# Sheet.net
KiCad netlist of a schematic drawn in Altium Designer
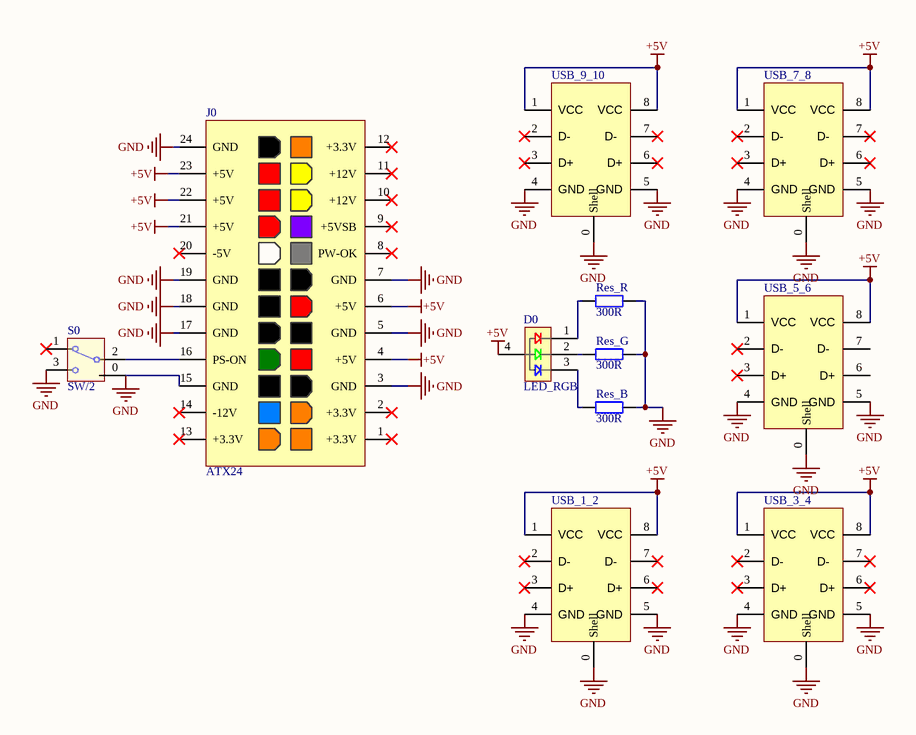
[diagram p0: Sheet.SchDoc]

(export (version "E")
  (design (tool "Eeschema 10.0.6"))
  (components
    (comp (ref "D0") (value "LED_RGB") (footprint "LED_RGB_0805") (libsource (lib "LED") (part "LED_RGB")))
    (comp (ref "J0")
      (value "ATX24")
      (footprint "ATX24-5569")
      (description "ATX24_5569 供电母座")
      (libsource (lib "ATX") (part "ATX24_5569"))
    )
    (comp (ref "Res_B")
      (value "300R")
      (footprint "0805-1")
      (description "贴片电阻")
      (fields (field (name "Comment") "Res1") (field (name "PUBLISHER") "Altium Limited"))
      (libsource (lib "") (part "Res1_1"))
    )
    (comp (ref "Res_G")
      (value "300R")
      (footprint "0805-1")
      (description "贴片电阻")
      (fields (field (name "Comment") "Res1") (field (name "PUBLISHER") "Altium Limited"))
      (libsource (lib "Normal") (part "Res1"))
    )
    (comp (ref "Res_R")
      (value "300R")
      (footprint "0805-1")
      (description "贴片电阻")
      (fields (field (name "Comment") "Res1") (field (name "PUBLISHER") "Altium Limited"))
      (libsource (lib "") (part "Res1_1"))
    )
    (comp (ref "S0")
      (value "SW/2")
      (footprint "SW/2_SIP3_H")
      (description "2档拨动开关")
      (libsource (lib "Switch") (part "SW/2"))
    )
    (comp (ref "USB_1_2")
      (value "USB-A_P/2")
      (footprint "USB-A_P/2")
      (description "USB-A 双层 180度 母座")
      (libsource (lib "USB") (part "USB-A_P/2"))
    )
    (comp (ref "USB_3_4")
      (value "USB-A_P/2")
      (footprint "USB-A_P/2")
      (description "USB-A 双层 180度 母座")
      (libsource (lib "USB") (part "USB-A_P/2"))
    )
    (comp (ref "USB_5_6")
      (value "USB-A_P/2")
      (footprint "USB-A_P/2")
      (description "USB-A 双层 180度 母座")
      (libsource (lib "USB") (part "USB-A_P/2"))
    )
    (comp (ref "USB_7_8")
      (value "USB-A_P/2")
      (footprint "USB-A_P/2")
      (description "USB-A 双层 180度 母座")
      (libsource (lib "USB") (part "USB-A_P/2"))
    )
    (comp (ref "USB_9_10")
      (value "USB-A_P/2")
      (footprint "USB-A_P/2")
      (description "USB-A 双层 180度 母座")
      (libsource (lib "USB") (part "USB-A_P/2"))
    )
  )
  (nets
    (net (code "1") (name "+5V") (class "Default")
      (node (ref "D0") (pin "4") (pinfunction "4_4") (pintype "passive"))
      (node (ref "J0") (pin "21") (pinfunction "+5V_21") (pintype "passive"))
      (node (ref "J0") (pin "22") (pinfunction "+5V_22") (pintype "passive"))
      (node (ref "J0") (pin "23") (pinfunction "+5V_23") (pintype "passive"))
      (node (ref "J0") (pin "4") (pinfunction "+5V_4") (pintype "passive"))
      (node (ref "J0") (pin "6") (pinfunction "+5V_6") (pintype "passive"))
      (node (ref "USB_1_2") (pin "1") (pinfunction "VCC_1") (pintype "passive"))
      (node (ref "USB_1_2") (pin "8") (pinfunction "VCC_8") (pintype "passive"))
      (node (ref "USB_3_4") (pin "1") (pinfunction "VCC_1") (pintype "passive"))
      (node (ref "USB_3_4") (pin "8") (pinfunction "VCC_8") (pintype "passive"))
      (node (ref "USB_5_6") (pin "1") (pinfunction "VCC_1") (pintype "passive"))
      (node (ref "USB_5_6") (pin "8") (pinfunction "VCC_8") (pintype "passive"))
      (node (ref "USB_7_8") (pin "1") (pinfunction "VCC_1") (pintype "passive"))
      (node (ref "USB_7_8") (pin "8") (pinfunction "VCC_8") (pintype "passive"))
      (node (ref "USB_9_10") (pin "1") (pinfunction "VCC_1") (pintype "passive"))
      (node (ref "USB_9_10") (pin "8") (pinfunction "VCC_8") (pintype "passive"))
    )
    (net (code "2") (name "GND") (class "Default")
      (node (ref "J0") (pin "15") (pinfunction "GND_15") (pintype "passive"))
      (node (ref "J0") (pin "17") (pinfunction "GND_17") (pintype "passive"))
      (node (ref "J0") (pin "18") (pinfunction "GND_18") (pintype "passive"))
      (node (ref "J0") (pin "19") (pinfunction "GND_19") (pintype "passive"))
      (node (ref "J0") (pin "24") (pinfunction "GND_24") (pintype "passive"))
      (node (ref "J0") (pin "3") (pinfunction "GND_3") (pintype "passive"))
      (node (ref "J0") (pin "5") (pinfunction "GND_5") (pintype "passive"))
      (node (ref "J0") (pin "7") (pinfunction "GND_7") (pintype "passive"))
      (node (ref "Res_B") (pin "1") (pinfunction "1_1") (pintype "passive"))
      (node (ref "Res_G") (pin "2") (pinfunction "2_2") (pintype "passive"))
      (node (ref "Res_R") (pin "1") (pinfunction "1_1") (pintype "passive"))
      (node (ref "S0") (pin "0") (pinfunction "0_0") (pintype "passive"))
      (node (ref "S0") (pin "3") (pinfunction "3_3") (pintype "passive"))
      (node (ref "USB_1_2") (pin "0") (pinfunction "Shell_0") (pintype "passive"))
      (node (ref "USB_1_2") (pin "4") (pinfunction "GND_4") (pintype "passive"))
      (node (ref "USB_1_2") (pin "5") (pinfunction "GND_5") (pintype "passive"))
      (node (ref "USB_3_4") (pin "0") (pinfunction "Shell_0") (pintype "passive"))
      (node (ref "USB_3_4") (pin "4") (pinfunction "GND_4") (pintype "passive"))
      (node (ref "USB_3_4") (pin "5") (pinfunction "GND_5") (pintype "passive"))
      (node (ref "USB_5_6") (pin "0") (pinfunction "Shell_0") (pintype "passive"))
      (node (ref "USB_5_6") (pin "4") (pinfunction "GND_4") (pintype "passive"))
      (node (ref "USB_5_6") (pin "5") (pinfunction "GND_5") (pintype "passive"))
      (node (ref "USB_7_8") (pin "0") (pinfunction "Shell_0") (pintype "passive"))
      (node (ref "USB_7_8") (pin "4") (pinfunction "GND_4") (pintype "passive"))
      (node (ref "USB_7_8") (pin "5") (pinfunction "GND_5") (pintype "passive"))
      (node (ref "USB_9_10") (pin "0") (pinfunction "Shell_0") (pintype "passive"))
      (node (ref "USB_9_10") (pin "4") (pinfunction "GND_4") (pintype "passive"))
      (node (ref "USB_9_10") (pin "5") (pinfunction "GND_5") (pintype "passive"))
    )
    (net (code "3") (name "Net-(D0-Pad1)") (class "Default")
      (node (ref "D0") (pin "1") (pinfunction "1_1") (pintype "passive"))
      (node (ref "Res_R") (pin "2") (pinfunction "2_2") (pintype "passive"))
    )
    (net (code "4") (name "Net-(D0-Pad2)") (class "Default")
      (node (ref "D0") (pin "2") (pinfunction "2_2") (pintype "passive"))
      (node (ref "Res_G") (pin "1") (pinfunction "1_1") (pintype "passive"))
    )
    (net (code "5") (name "Net-(D0-Pad3)") (class "Default")
      (node (ref "D0") (pin "3") (pinfunction "3_3") (pintype "passive"))
      (node (ref "Res_B") (pin "2") (pinfunction "2_2") (pintype "passive"))
    )
    (net (code "6") (name "Net-(J0-PS-ON)") (class "Default")
      (node (ref "J0") (pin "16") (pinfunction "PS-ON_16") (pintype "passive"))
      (node (ref "S0") (pin "2") (pinfunction "2_2") (pintype "passive"))
    )
    (net (code "7") (name "unconnected-(J0-+3.3V-Pad1)") (class "Default")
      (node (ref "J0") (pin "1") (pinfunction "+3.3V_1") (pintype "passive+no_connect"))
    )
    (net (code "8") (name "unconnected-(J0-+3.3V-Pad2)") (class "Default")
      (node (ref "J0") (pin "2") (pinfunction "+3.3V_2") (pintype "passive+no_connect"))
    )
    (net (code "9") (name "unconnected-(J0-+3.3V-Pad12)") (class "Default")
      (node (ref "J0") (pin "12") (pinfunction "+3.3V_12") (pintype "passive+no_connect"))
    )
    (net (code "10") (name "unconnected-(J0-+3.3V-Pad13)") (class "Default")
      (node (ref "J0") (pin "13") (pinfunction "+3.3V_13") (pintype "passive+no_connect"))
    )
    (net (code "11") (name "unconnected-(J0-+5VSB-Pad9)") (class "Default")
      (node (ref "J0") (pin "9") (pinfunction "+5VSB_9") (pintype "passive+no_connect"))
    )
    (net (code "12") (name "unconnected-(J0-+12V-Pad10)") (class "Default")
      (node (ref "J0") (pin "10") (pinfunction "+12V_10") (pintype "passive+no_connect"))
    )
    (net (code "13") (name "unconnected-(J0-+12V-Pad11)") (class "Default")
      (node (ref "J0") (pin "11") (pinfunction "+12V_11") (pintype "passive+no_connect"))
    )
    (net (code "14") (name "unconnected-(J0--5V-Pad20)") (class "Default")
      (node (ref "J0") (pin "20") (pinfunction "-5V_20") (pintype "passive+no_connect"))
    )
    (net (code "15") (name "unconnected-(J0--12V-Pad14)") (class "Default")
      (node (ref "J0") (pin "14") (pinfunction "-12V_14") (pintype "passive+no_connect"))
    )
    (net (code "16") (name "unconnected-(J0-PW-OK-Pad8)") (class "Default")
      (node (ref "J0") (pin "8") (pinfunction "PW-OK_8") (pintype "passive+no_connect"))
    )
    (net (code "17") (name "unconnected-(S0-Pad1)") (class "Default")
      (node (ref "S0") (pin "1") (pinfunction "1_1") (pintype "passive+no_connect"))
    )
    (net (code "18") (name "unconnected-(USB_1_2-D+-Pad3)") (class "Default")
      (node (ref "USB_1_2") (pin "3") (pinfunction "D+_3") (pintype "passive+no_connect"))
    )
    (net (code "19") (name "unconnected-(USB_1_2-D+-Pad6)") (class "Default")
      (node (ref "USB_1_2") (pin "6") (pinfunction "D+_6") (pintype "passive+no_connect"))
    )
    (net (code "20") (name "unconnected-(USB_1_2-D--Pad2)") (class "Default")
      (node (ref "USB_1_2") (pin "2") (pinfunction "D-_2") (pintype "passive+no_connect"))
    )
    (net (code "21") (name "unconnected-(USB_1_2-D--Pad7)") (class "Default")
      (node (ref "USB_1_2") (pin "7") (pinfunction "D-_7") (pintype "passive+no_connect"))
    )
    (net (code "22") (name "unconnected-(USB_3_4-D+-Pad3)") (class "Default")
      (node (ref "USB_3_4") (pin "3") (pinfunction "D+_3") (pintype "passive+no_connect"))
    )
    (net (code "23") (name "unconnected-(USB_3_4-D+-Pad6)") (class "Default")
      (node (ref "USB_3_4") (pin "6") (pinfunction "D+_6") (pintype "passive+no_connect"))
    )
    (net (code "24") (name "unconnected-(USB_3_4-D--Pad2)") (class "Default")
      (node (ref "USB_3_4") (pin "2") (pinfunction "D-_2") (pintype "passive+no_connect"))
    )
    (net (code "25") (name "unconnected-(USB_3_4-D--Pad7)") (class "Default")
      (node (ref "USB_3_4") (pin "7") (pinfunction "D-_7") (pintype "passive+no_connect"))
    )
    (net (code "26") (name "unconnected-(USB_5_6-D+-Pad3)") (class "Default")
      (node (ref "USB_5_6") (pin "3") (pinfunction "D+_3") (pintype "passive+no_connect"))
    )
    (net (code "27") (name "unconnected-(USB_5_6-D+-Pad6)") (class "Default")
      (node (ref "USB_5_6") (pin "6") (pinfunction "D+_6") (pintype "passive"))
    )
    (net (code "28") (name "unconnected-(USB_5_6-D--Pad2)") (class "Default")
      (node (ref "USB_5_6") (pin "2") (pinfunction "D-_2") (pintype "passive+no_connect"))
    )
    (net (code "29") (name "unconnected-(USB_5_6-D--Pad7)") (class "Default")
      (node (ref "USB_5_6") (pin "7") (pinfunction "D-_7") (pintype "passive"))
    )
    (net (code "30") (name "unconnected-(USB_7_8-D+-Pad3)") (class "Default")
      (node (ref "USB_7_8") (pin "3") (pinfunction "D+_3") (pintype "passive+no_connect"))
    )
    (net (code "31") (name "unconnected-(USB_7_8-D+-Pad6)") (class "Default")
      (node (ref "USB_7_8") (pin "6") (pinfunction "D+_6") (pintype "passive+no_connect"))
    )
    (net (code "32") (name "unconnected-(USB_7_8-D--Pad2)") (class "Default")
      (node (ref "USB_7_8") (pin "2") (pinfunction "D-_2") (pintype "passive+no_connect"))
    )
    (net (code "33") (name "unconnected-(USB_7_8-D--Pad7)") (class "Default")
      (node (ref "USB_7_8") (pin "7") (pinfunction "D-_7") (pintype "passive+no_connect"))
    )
    (net (code "34") (name "unconnected-(USB_9_10-D+-Pad3)") (class "Default")
      (node (ref "USB_9_10") (pin "3") (pinfunction "D+_3") (pintype "passive+no_connect"))
    )
    (net (code "35") (name "unconnected-(USB_9_10-D+-Pad6)") (class "Default")
      (node (ref "USB_9_10") (pin "6") (pinfunction "D+_6") (pintype "passive+no_connect"))
    )
    (net (code "36") (name "unconnected-(USB_9_10-D--Pad2)") (class "Default")
      (node (ref "USB_9_10") (pin "2") (pinfunction "D-_2") (pintype "passive+no_connect"))
    )
    (net (code "37") (name "unconnected-(USB_9_10-D--Pad7)") (class "Default")
      (node (ref "USB_9_10") (pin "7") (pinfunction "D-_7") (pintype "passive+no_connect"))
    )
  )
)
